# pi.net
KiCad netlist of a schematic drawn in EAGLE
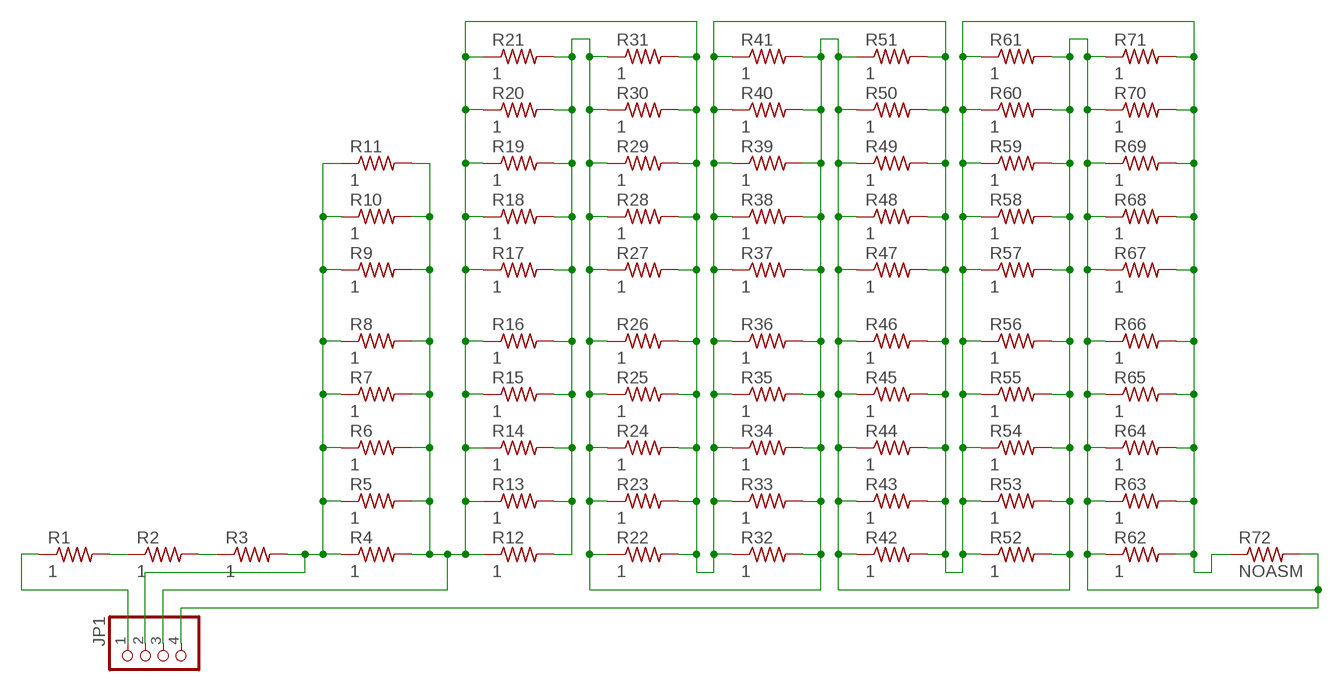
[diagram p0: schematic, sheet 1]

(export (version "E")
  (design (tool "Eeschema 10.0.6"))
  (components
    (comp (ref "JP1")
      (value "PINHD-1X4")
      (footprint "eagle-import:1X04")
      (libsource (lib "eagle-import") (part "PINHD-1X4"))
    )
    (comp (ref "R1")
      (value "1")
      (footprint "eagle-import:R0603")
      (libsource (lib "eagle-import") (part "R-US_R0603"))
    )
    (comp (ref "R2")
      (value "1")
      (footprint "eagle-import:R0603")
      (libsource (lib "eagle-import") (part "R-US_R0603"))
    )
    (comp (ref "R3")
      (value "1")
      (footprint "eagle-import:R0603")
      (libsource (lib "eagle-import") (part "R-US_R0603"))
    )
    (comp (ref "R4")
      (value "1")
      (footprint "eagle-import:R0603")
      (libsource (lib "eagle-import") (part "R-US_R0603"))
    )
    (comp (ref "R5")
      (value "1")
      (footprint "eagle-import:R0603")
      (libsource (lib "eagle-import") (part "R-US_R0603"))
    )
    (comp (ref "R6")
      (value "1")
      (footprint "eagle-import:R0603")
      (libsource (lib "eagle-import") (part "R-US_R0603"))
    )
    (comp (ref "R7")
      (value "1")
      (footprint "eagle-import:R0603")
      (libsource (lib "eagle-import") (part "R-US_R0603"))
    )
    (comp (ref "R8")
      (value "1")
      (footprint "eagle-import:R0603")
      (libsource (lib "eagle-import") (part "R-US_R0603"))
    )
    (comp (ref "R9")
      (value "1")
      (footprint "eagle-import:R0603")
      (libsource (lib "eagle-import") (part "R-US_R0603"))
    )
    (comp (ref "R10")
      (value "1")
      (footprint "eagle-import:R0603")
      (libsource (lib "eagle-import") (part "R-US_R0603"))
    )
    (comp (ref "R11")
      (value "1")
      (footprint "eagle-import:R0603")
      (libsource (lib "eagle-import") (part "R-US_R0603"))
    )
    (comp (ref "R12")
      (value "1")
      (footprint "eagle-import:R0603")
      (libsource (lib "eagle-import") (part "R-US_R0603"))
    )
    (comp (ref "R13")
      (value "1")
      (footprint "eagle-import:R0603")
      (libsource (lib "eagle-import") (part "R-US_R0603"))
    )
    (comp (ref "R14")
      (value "1")
      (footprint "eagle-import:R0603")
      (libsource (lib "eagle-import") (part "R-US_R0603"))
    )
    (comp (ref "R15")
      (value "1")
      (footprint "eagle-import:R0603")
      (libsource (lib "eagle-import") (part "R-US_R0603"))
    )
    (comp (ref "R16")
      (value "1")
      (footprint "eagle-import:R0603")
      (libsource (lib "eagle-import") (part "R-US_R0603"))
    )
    (comp (ref "R17")
      (value "1")
      (footprint "eagle-import:R0603")
      (libsource (lib "eagle-import") (part "R-US_R0603"))
    )
    (comp (ref "R18")
      (value "1")
      (footprint "eagle-import:R0603")
      (libsource (lib "eagle-import") (part "R-US_R0603"))
    )
    (comp (ref "R19")
      (value "1")
      (footprint "eagle-import:R0603")
      (libsource (lib "eagle-import") (part "R-US_R0603"))
    )
    (comp (ref "R20")
      (value "1")
      (footprint "eagle-import:R0603")
      (libsource (lib "eagle-import") (part "R-US_R0603"))
    )
    (comp (ref "R21")
      (value "1")
      (footprint "eagle-import:R0603")
      (libsource (lib "eagle-import") (part "R-US_R0603"))
    )
    (comp (ref "R22")
      (value "1")
      (footprint "eagle-import:R0603")
      (libsource (lib "eagle-import") (part "R-US_R0603"))
    )
    (comp (ref "R23")
      (value "1")
      (footprint "eagle-import:R0603")
      (libsource (lib "eagle-import") (part "R-US_R0603"))
    )
    (comp (ref "R24")
      (value "1")
      (footprint "eagle-import:R0603")
      (libsource (lib "eagle-import") (part "R-US_R0603"))
    )
    (comp (ref "R25")
      (value "1")
      (footprint "eagle-import:R0603")
      (libsource (lib "eagle-import") (part "R-US_R0603"))
    )
    (comp (ref "R26")
      (value "1")
      (footprint "eagle-import:R0603")
      (libsource (lib "eagle-import") (part "R-US_R0603"))
    )
    (comp (ref "R27")
      (value "1")
      (footprint "eagle-import:R0603")
      (libsource (lib "eagle-import") (part "R-US_R0603"))
    )
    (comp (ref "R28")
      (value "1")
      (footprint "eagle-import:R0603")
      (libsource (lib "eagle-import") (part "R-US_R0603"))
    )
    (comp (ref "R29")
      (value "1")
      (footprint "eagle-import:R0603")
      (libsource (lib "eagle-import") (part "R-US_R0603"))
    )
    (comp (ref "R30")
      (value "1")
      (footprint "eagle-import:R0603")
      (libsource (lib "eagle-import") (part "R-US_R0603"))
    )
    (comp (ref "R31")
      (value "1")
      (footprint "eagle-import:R0603")
      (libsource (lib "eagle-import") (part "R-US_R0603"))
    )
    (comp (ref "R32")
      (value "1")
      (footprint "eagle-import:R0603")
      (libsource (lib "eagle-import") (part "R-US_R0603"))
    )
    (comp (ref "R33")
      (value "1")
      (footprint "eagle-import:R0603")
      (libsource (lib "eagle-import") (part "R-US_R0603"))
    )
    (comp (ref "R34")
      (value "1")
      (footprint "eagle-import:R0603")
      (libsource (lib "eagle-import") (part "R-US_R0603"))
    )
    (comp (ref "R35")
      (value "1")
      (footprint "eagle-import:R0603")
      (libsource (lib "eagle-import") (part "R-US_R0603"))
    )
    (comp (ref "R36")
      (value "1")
      (footprint "eagle-import:R0603")
      (libsource (lib "eagle-import") (part "R-US_R0603"))
    )
    (comp (ref "R37")
      (value "1")
      (footprint "eagle-import:R0603")
      (libsource (lib "eagle-import") (part "R-US_R0603"))
    )
    (comp (ref "R38")
      (value "1")
      (footprint "eagle-import:R0603")
      (libsource (lib "eagle-import") (part "R-US_R0603"))
    )
    (comp (ref "R39")
      (value "1")
      (footprint "eagle-import:R0603")
      (libsource (lib "eagle-import") (part "R-US_R0603"))
    )
    (comp (ref "R40")
      (value "1")
      (footprint "eagle-import:R0603")
      (libsource (lib "eagle-import") (part "R-US_R0603"))
    )
    (comp (ref "R41")
      (value "1")
      (footprint "eagle-import:R0603")
      (libsource (lib "eagle-import") (part "R-US_R0603"))
    )
    (comp (ref "R42")
      (value "1")
      (footprint "eagle-import:R0603")
      (libsource (lib "eagle-import") (part "R-US_R0603"))
    )
    (comp (ref "R43")
      (value "1")
      (footprint "eagle-import:R0603")
      (libsource (lib "eagle-import") (part "R-US_R0603"))
    )
    (comp (ref "R44")
      (value "1")
      (footprint "eagle-import:R0603")
      (libsource (lib "eagle-import") (part "R-US_R0603"))
    )
    (comp (ref "R45")
      (value "1")
      (footprint "eagle-import:R0603")
      (libsource (lib "eagle-import") (part "R-US_R0603"))
    )
    (comp (ref "R46")
      (value "1")
      (footprint "eagle-import:R0603")
      (libsource (lib "eagle-import") (part "R-US_R0603"))
    )
    (comp (ref "R47")
      (value "1")
      (footprint "eagle-import:R0603")
      (libsource (lib "eagle-import") (part "R-US_R0603"))
    )
    (comp (ref "R48")
      (value "1")
      (footprint "eagle-import:R0603")
      (libsource (lib "eagle-import") (part "R-US_R0603"))
    )
    (comp (ref "R49")
      (value "1")
      (footprint "eagle-import:R0603")
      (libsource (lib "eagle-import") (part "R-US_R0603"))
    )
    (comp (ref "R50")
      (value "1")
      (footprint "eagle-import:R0603")
      (libsource (lib "eagle-import") (part "R-US_R0603"))
    )
    (comp (ref "R51")
      (value "1")
      (footprint "eagle-import:R0603")
      (libsource (lib "eagle-import") (part "R-US_R0603"))
    )
    (comp (ref "R52")
      (value "1")
      (footprint "eagle-import:R0603")
      (libsource (lib "eagle-import") (part "R-US_R0603"))
    )
    (comp (ref "R53")
      (value "1")
      (footprint "eagle-import:R0603")
      (libsource (lib "eagle-import") (part "R-US_R0603"))
    )
    (comp (ref "R54")
      (value "1")
      (footprint "eagle-import:R0603")
      (libsource (lib "eagle-import") (part "R-US_R0603"))
    )
    (comp (ref "R55")
      (value "1")
      (footprint "eagle-import:R0603")
      (libsource (lib "eagle-import") (part "R-US_R0603"))
    )
    (comp (ref "R56")
      (value "1")
      (footprint "eagle-import:R0603")
      (libsource (lib "eagle-import") (part "R-US_R0603"))
    )
    (comp (ref "R57")
      (value "1")
      (footprint "eagle-import:R0603")
      (libsource (lib "eagle-import") (part "R-US_R0603"))
    )
    (comp (ref "R58")
      (value "1")
      (footprint "eagle-import:R0603")
      (libsource (lib "eagle-import") (part "R-US_R0603"))
    )
    (comp (ref "R59")
      (value "1")
      (footprint "eagle-import:R0603")
      (libsource (lib "eagle-import") (part "R-US_R0603"))
    )
    (comp (ref "R60")
      (value "1")
      (footprint "eagle-import:R0603")
      (libsource (lib "eagle-import") (part "R-US_R0603"))
    )
    (comp (ref "R61")
      (value "1")
      (footprint "eagle-import:R0603")
      (libsource (lib "eagle-import") (part "R-US_R0603"))
    )
    (comp (ref "R62")
      (value "1")
      (footprint "eagle-import:R0603")
      (libsource (lib "eagle-import") (part "R-US_R0603"))
    )
    (comp (ref "R63")
      (value "1")
      (footprint "eagle-import:R0603")
      (libsource (lib "eagle-import") (part "R-US_R0603"))
    )
    (comp (ref "R64")
      (value "1")
      (footprint "eagle-import:R0603")
      (libsource (lib "eagle-import") (part "R-US_R0603"))
    )
    (comp (ref "R65")
      (value "1")
      (footprint "eagle-import:R0603")
      (libsource (lib "eagle-import") (part "R-US_R0603"))
    )
    (comp (ref "R66")
      (value "1")
      (footprint "eagle-import:R0603")
      (libsource (lib "eagle-import") (part "R-US_R0603"))
    )
    (comp (ref "R67")
      (value "1")
      (footprint "eagle-import:R0603")
      (libsource (lib "eagle-import") (part "R-US_R0603"))
    )
    (comp (ref "R68")
      (value "1")
      (footprint "eagle-import:R0603")
      (libsource (lib "eagle-import") (part "R-US_R0603"))
    )
    (comp (ref "R69")
      (value "1")
      (footprint "eagle-import:R0603")
      (libsource (lib "eagle-import") (part "R-US_R0603"))
    )
    (comp (ref "R70")
      (value "1")
      (footprint "eagle-import:R0603")
      (libsource (lib "eagle-import") (part "R-US_R0603"))
    )
    (comp (ref "R71")
      (value "1")
      (footprint "eagle-import:R0603")
      (libsource (lib "eagle-import") (part "R-US_R0603"))
    )
    (comp (ref "R72")
      (value "NOASM")
      (footprint "eagle-import:R0603")
      (libsource (lib "eagle-import") (part "R-US_R0603"))
    )
  )
  (nets
    (net (code "1") (name "Net-(JP1-Pad1)") (class "Default")
      (node (ref "JP1") (pin "1") (pinfunction "1_1") (pintype "passive"))
      (node (ref "R1") (pin "1") (pinfunction "1_1") (pintype "passive"))
    )
    (net (code "2") (name "Net-(JP1-Pad2)") (class "Default")
      (node (ref "JP1") (pin "2") (pinfunction "2_2") (pintype "passive"))
      (node (ref "R10") (pin "1") (pinfunction "1_1") (pintype "passive"))
      (node (ref "R11") (pin "1") (pinfunction "1_1") (pintype "passive"))
      (node (ref "R3") (pin "2") (pinfunction "2_2") (pintype "passive"))
      (node (ref "R4") (pin "1") (pinfunction "1_1") (pintype "passive"))
      (node (ref "R5") (pin "1") (pinfunction "1_1") (pintype "passive"))
      (node (ref "R6") (pin "1") (pinfunction "1_1") (pintype "passive"))
      (node (ref "R7") (pin "1") (pinfunction "1_1") (pintype "passive"))
      (node (ref "R8") (pin "1") (pinfunction "1_1") (pintype "passive"))
      (node (ref "R9") (pin "1") (pinfunction "1_1") (pintype "passive"))
    )
    (net (code "3") (name "Net-(JP1-Pad3)") (class "Default")
      (node (ref "JP1") (pin "3") (pinfunction "3_3") (pintype "passive"))
      (node (ref "R10") (pin "2") (pinfunction "2_2") (pintype "passive"))
      (node (ref "R11") (pin "2") (pinfunction "2_2") (pintype "passive"))
      (node (ref "R12") (pin "1") (pinfunction "1_1") (pintype "passive"))
      (node (ref "R13") (pin "1") (pinfunction "1_1") (pintype "passive"))
      (node (ref "R14") (pin "1") (pinfunction "1_1") (pintype "passive"))
      (node (ref "R15") (pin "1") (pinfunction "1_1") (pintype "passive"))
      (node (ref "R16") (pin "1") (pinfunction "1_1") (pintype "passive"))
      (node (ref "R17") (pin "1") (pinfunction "1_1") (pintype "passive"))
      (node (ref "R18") (pin "1") (pinfunction "1_1") (pintype "passive"))
      (node (ref "R19") (pin "1") (pinfunction "1_1") (pintype "passive"))
      (node (ref "R20") (pin "1") (pinfunction "1_1") (pintype "passive"))
      (node (ref "R21") (pin "1") (pinfunction "1_1") (pintype "passive"))
      (node (ref "R22") (pin "2") (pinfunction "2_2") (pintype "passive"))
      (node (ref "R23") (pin "2") (pinfunction "2_2") (pintype "passive"))
      (node (ref "R24") (pin "2") (pinfunction "2_2") (pintype "passive"))
      (node (ref "R25") (pin "2") (pinfunction "2_2") (pintype "passive"))
      (node (ref "R26") (pin "2") (pinfunction "2_2") (pintype "passive"))
      (node (ref "R27") (pin "2") (pinfunction "2_2") (pintype "passive"))
      (node (ref "R28") (pin "2") (pinfunction "2_2") (pintype "passive"))
      (node (ref "R29") (pin "2") (pinfunction "2_2") (pintype "passive"))
      (node (ref "R30") (pin "2") (pinfunction "2_2") (pintype "passive"))
      (node (ref "R31") (pin "2") (pinfunction "2_2") (pintype "passive"))
      (node (ref "R32") (pin "1") (pinfunction "1_1") (pintype "passive"))
      (node (ref "R33") (pin "1") (pinfunction "1_1") (pintype "passive"))
      (node (ref "R34") (pin "1") (pinfunction "1_1") (pintype "passive"))
      (node (ref "R35") (pin "1") (pinfunction "1_1") (pintype "passive"))
      (node (ref "R36") (pin "1") (pinfunction "1_1") (pintype "passive"))
      (node (ref "R37") (pin "1") (pinfunction "1_1") (pintype "passive"))
      (node (ref "R38") (pin "1") (pinfunction "1_1") (pintype "passive"))
      (node (ref "R39") (pin "1") (pinfunction "1_1") (pintype "passive"))
      (node (ref "R4") (pin "2") (pinfunction "2_2") (pintype "passive"))
      (node (ref "R40") (pin "1") (pinfunction "1_1") (pintype "passive"))
      (node (ref "R41") (pin "1") (pinfunction "1_1") (pintype "passive"))
      (node (ref "R42") (pin "2") (pinfunction "2_2") (pintype "passive"))
      (node (ref "R43") (pin "2") (pinfunction "2_2") (pintype "passive"))
      (node (ref "R44") (pin "2") (pinfunction "2_2") (pintype "passive"))
      (node (ref "R45") (pin "2") (pinfunction "2_2") (pintype "passive"))
      (node (ref "R46") (pin "2") (pinfunction "2_2") (pintype "passive"))
      (node (ref "R47") (pin "2") (pinfunction "2_2") (pintype "passive"))
      (node (ref "R48") (pin "2") (pinfunction "2_2") (pintype "passive"))
      (node (ref "R49") (pin "2") (pinfunction "2_2") (pintype "passive"))
      (node (ref "R5") (pin "2") (pinfunction "2_2") (pintype "passive"))
      (node (ref "R50") (pin "2") (pinfunction "2_2") (pintype "passive"))
      (node (ref "R51") (pin "2") (pinfunction "2_2") (pintype "passive"))
      (node (ref "R52") (pin "1") (pinfunction "1_1") (pintype "passive"))
      (node (ref "R53") (pin "1") (pinfunction "1_1") (pintype "passive"))
      (node (ref "R54") (pin "1") (pinfunction "1_1") (pintype "passive"))
      (node (ref "R55") (pin "1") (pinfunction "1_1") (pintype "passive"))
      (node (ref "R56") (pin "1") (pinfunction "1_1") (pintype "passive"))
      (node (ref "R57") (pin "1") (pinfunction "1_1") (pintype "passive"))
      (node (ref "R58") (pin "1") (pinfunction "1_1") (pintype "passive"))
      (node (ref "R59") (pin "1") (pinfunction "1_1") (pintype "passive"))
      (node (ref "R6") (pin "2") (pinfunction "2_2") (pintype "passive"))
      (node (ref "R60") (pin "1") (pinfunction "1_1") (pintype "passive"))
      (node (ref "R61") (pin "1") (pinfunction "1_1") (pintype "passive"))
      (node (ref "R62") (pin "2") (pinfunction "2_2") (pintype "passive"))
      (node (ref "R63") (pin "2") (pinfunction "2_2") (pintype "passive"))
      (node (ref "R64") (pin "2") (pinfunction "2_2") (pintype "passive"))
      (node (ref "R65") (pin "2") (pinfunction "2_2") (pintype "passive"))
      (node (ref "R66") (pin "2") (pinfunction "2_2") (pintype "passive"))
      (node (ref "R67") (pin "2") (pinfunction "2_2") (pintype "passive"))
      (node (ref "R68") (pin "2") (pinfunction "2_2") (pintype "passive"))
      (node (ref "R69") (pin "2") (pinfunction "2_2") (pintype "passive"))
      (node (ref "R7") (pin "2") (pinfunction "2_2") (pintype "passive"))
      (node (ref "R70") (pin "2") (pinfunction "2_2") (pintype "passive"))
      (node (ref "R71") (pin "2") (pinfunction "2_2") (pintype "passive"))
      (node (ref "R72") (pin "1") (pinfunction "1_1") (pintype "passive"))
      (node (ref "R8") (pin "2") (pinfunction "2_2") (pintype "passive"))
      (node (ref "R9") (pin "2") (pinfunction "2_2") (pintype "passive"))
    )
    (net (code "4") (name "Net-(JP1-Pad4)") (class "Default")
      (node (ref "JP1") (pin "4") (pinfunction "4_4") (pintype "passive"))
      (node (ref "R12") (pin "2") (pinfunction "2_2") (pintype "passive"))
      (node (ref "R13") (pin "2") (pinfunction "2_2") (pintype "passive"))
      (node (ref "R14") (pin "2") (pinfunction "2_2") (pintype "passive"))
      (node (ref "R15") (pin "2") (pinfunction "2_2") (pintype "passive"))
      (node (ref "R16") (pin "2") (pinfunction "2_2") (pintype "passive"))
      (node (ref "R17") (pin "2") (pinfunction "2_2") (pintype "passive"))
      (node (ref "R18") (pin "2") (pinfunction "2_2") (pintype "passive"))
      (node (ref "R19") (pin "2") (pinfunction "2_2") (pintype "passive"))
      (node (ref "R20") (pin "2") (pinfunction "2_2") (pintype "passive"))
      (node (ref "R21") (pin "2") (pinfunction "2_2") (pintype "passive"))
      (node (ref "R22") (pin "1") (pinfunction "1_1") (pintype "passive"))
      (node (ref "R23") (pin "1") (pinfunction "1_1") (pintype "passive"))
      (node (ref "R24") (pin "1") (pinfunction "1_1") (pintype "passive"))
      (node (ref "R25") (pin "1") (pinfunction "1_1") (pintype "passive"))
      (node (ref "R26") (pin "1") (pinfunction "1_1") (pintype "passive"))
      (node (ref "R27") (pin "1") (pinfunction "1_1") (pintype "passive"))
      (node (ref "R28") (pin "1") (pinfunction "1_1") (pintype "passive"))
      (node (ref "R29") (pin "1") (pinfunction "1_1") (pintype "passive"))
      (node (ref "R30") (pin "1") (pinfunction "1_1") (pintype "passive"))
      (node (ref "R31") (pin "1") (pinfunction "1_1") (pintype "passive"))
      (node (ref "R32") (pin "2") (pinfunction "2_2") (pintype "passive"))
      (node (ref "R33") (pin "2") (pinfunction "2_2") (pintype "passive"))
      (node (ref "R34") (pin "2") (pinfunction "2_2") (pintype "passive"))
      (node (ref "R35") (pin "2") (pinfunction "2_2") (pintype "passive"))
      (node (ref "R36") (pin "2") (pinfunction "2_2") (pintype "passive"))
      (node (ref "R37") (pin "2") (pinfunction "2_2") (pintype "passive"))
      (node (ref "R38") (pin "2") (pinfunction "2_2") (pintype "passive"))
      (node (ref "R39") (pin "2") (pinfunction "2_2") (pintype "passive"))
      (node (ref "R40") (pin "2") (pinfunction "2_2") (pintype "passive"))
      (node (ref "R41") (pin "2") (pinfunction "2_2") (pintype "passive"))
      (node (ref "R42") (pin "1") (pinfunction "1_1") (pintype "passive"))
      (node (ref "R43") (pin "1") (pinfunction "1_1") (pintype "passive"))
      (node (ref "R44") (pin "1") (pinfunction "1_1") (pintype "passive"))
      (node (ref "R45") (pin "1") (pinfunction "1_1") (pintype "passive"))
      (node (ref "R46") (pin "1") (pinfunction "1_1") (pintype "passive"))
      (node (ref "R47") (pin "1") (pinfunction "1_1") (pintype "passive"))
      (node (ref "R48") (pin "1") (pinfunction "1_1") (pintype "passive"))
      (node (ref "R49") (pin "1") (pinfunction "1_1") (pintype "passive"))
      (node (ref "R50") (pin "1") (pinfunction "1_1") (pintype "passive"))
      (node (ref "R51") (pin "1") (pinfunction "1_1") (pintype "passive"))
      (node (ref "R52") (pin "2") (pinfunction "2_2") (pintype "passive"))
      (node (ref "R53") (pin "2") (pinfunction "2_2") (pintype "passive"))
      (node (ref "R54") (pin "2") (pinfunction "2_2") (pintype "passive"))
      (node (ref "R55") (pin "2") (pinfunction "2_2") (pintype "passive"))
      (node (ref "R56") (pin "2") (pinfunction "2_2") (pintype "passive"))
      (node (ref "R57") (pin "2") (pinfunction "2_2") (pintype "passive"))
      (node (ref "R58") (pin "2") (pinfunction "2_2") (pintype "passive"))
      (node (ref "R59") (pin "2") (pinfunction "2_2") (pintype "passive"))
      (node (ref "R60") (pin "2") (pinfunction "2_2") (pintype "passive"))
      (node (ref "R61") (pin "2") (pinfunction "2_2") (pintype "passive"))
      (node (ref "R62") (pin "1") (pinfunction "1_1") (pintype "passive"))
      (node (ref "R63") (pin "1") (pinfunction "1_1") (pintype "passive"))
      (node (ref "R64") (pin "1") (pinfunction "1_1") (pintype "passive"))
      (node (ref "R65") (pin "1") (pinfunction "1_1") (pintype "passive"))
      (node (ref "R66") (pin "1") (pinfunction "1_1") (pintype "passive"))
      (node (ref "R67") (pin "1") (pinfunction "1_1") (pintype "passive"))
      (node (ref "R68") (pin "1") (pinfunction "1_1") (pintype "passive"))
      (node (ref "R69") (pin "1") (pinfunction "1_1") (pintype "passive"))
      (node (ref "R70") (pin "1") (pinfunction "1_1") (pintype "passive"))
      (node (ref "R71") (pin "1") (pinfunction "1_1") (pintype "passive"))
      (node (ref "R72") (pin "2") (pinfunction "2_2") (pintype "passive"))
    )
    (net (code "5") (name "Net-(R1-Pad2)") (class "Default")
      (node (ref "R1") (pin "2") (pinfunction "2_2") (pintype "passive"))
      (node (ref "R2") (pin "1") (pinfunction "1_1") (pintype "passive"))
    )
    (net (code "6") (name "Net-(R2-Pad2)") (class "Default")
      (node (ref "R2") (pin "2") (pinfunction "2_2") (pintype "passive"))
      (node (ref "R3") (pin "1") (pinfunction "1_1") (pintype "passive"))
    )
  )
)
